# VGA_sound.net
KiCad netlist of a schematic drawn in EAGLE
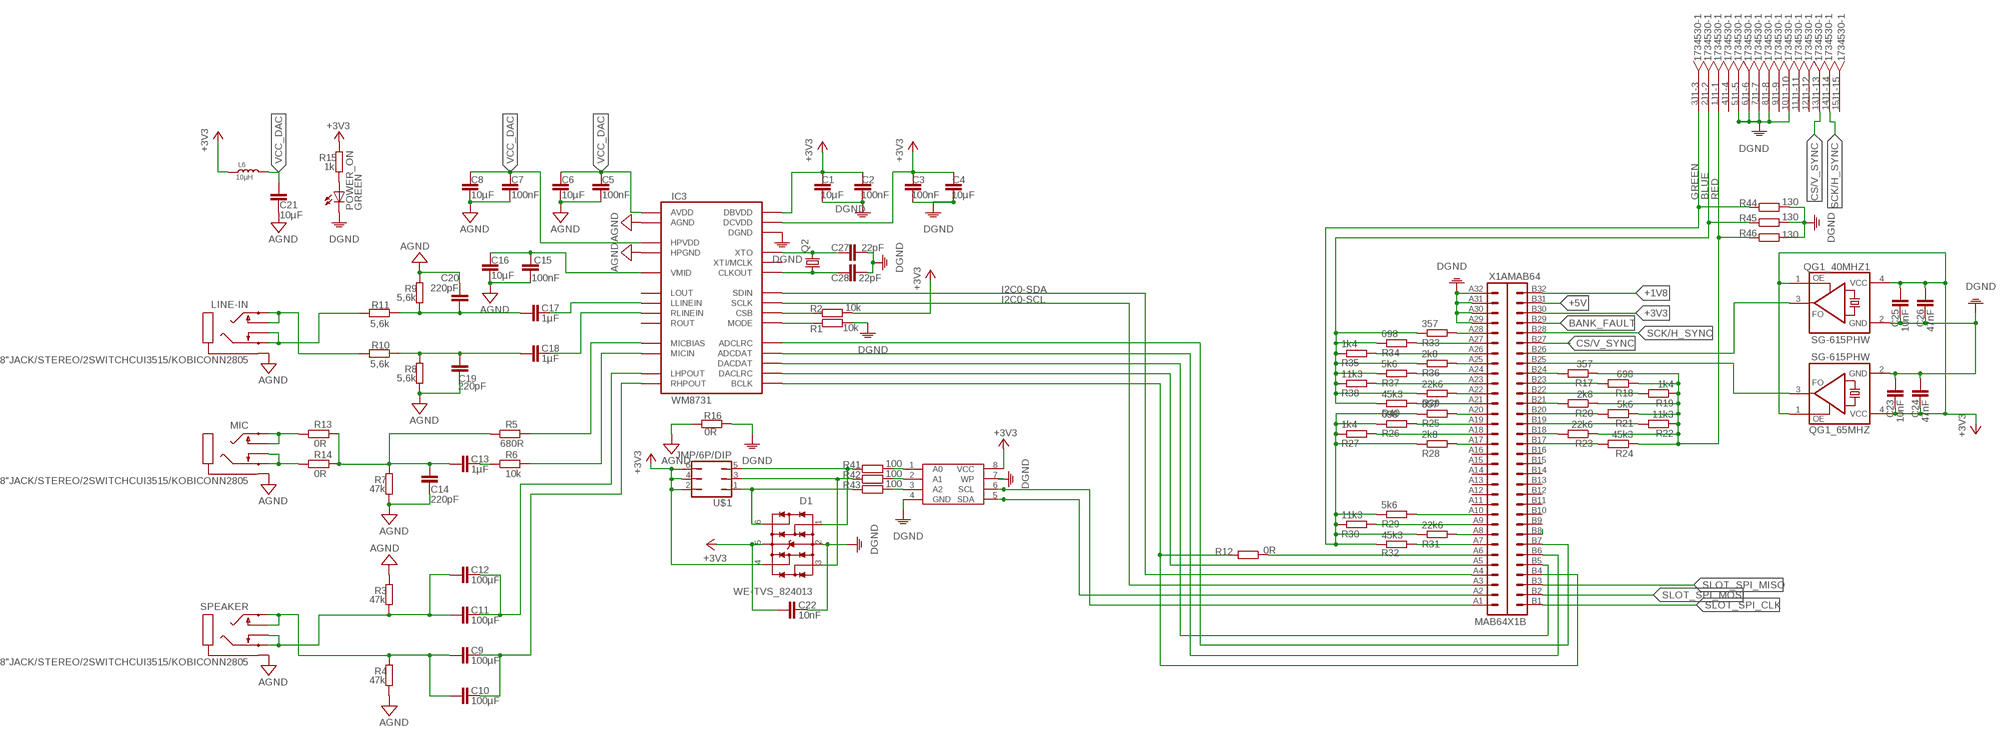
[diagram p0: schematic, sheet 1]

(export (version "E")
  (design (tool "Eeschema 10.0.6"))
  (components
    (comp (ref "C1")
      (value "10µF")
      (footprint "eagle-import:C0603")
      (libsource (lib "eagle-import") (part "C-EUC0603"))
    )
    (comp (ref "C2")
      (value "100nF")
      (footprint "eagle-import:C0603")
      (libsource (lib "eagle-import") (part "C-EUC0603"))
    )
    (comp (ref "C3")
      (value "100nF")
      (footprint "eagle-import:C0603K")
      (libsource (lib "eagle-import") (part "C-EUC0603K"))
    )
    (comp (ref "C4")
      (value "10µF")
      (footprint "eagle-import:C0603K")
      (libsource (lib "eagle-import") (part "C-EUC0603K"))
    )
    (comp (ref "C5")
      (value "100nF")
      (footprint "eagle-import:C0603K")
      (libsource (lib "eagle-import") (part "C-EUC0603K"))
    )
    (comp (ref "C6")
      (value "10µF")
      (footprint "eagle-import:C0603K")
      (libsource (lib "eagle-import") (part "C-EUC0603K"))
    )
    (comp (ref "C7")
      (value "100nF")
      (footprint "eagle-import:C0603K")
      (libsource (lib "eagle-import") (part "C-EUC0603K"))
    )
    (comp (ref "C8")
      (value "10µF")
      (footprint "eagle-import:C0603K")
      (libsource (lib "eagle-import") (part "C-EUC0603K"))
    )
    (comp (ref "C9")
      (value "100µF")
      (footprint "eagle-import:C1206")
      (libsource (lib "eagle-import") (part "C-EUC1206"))
    )
    (comp (ref "C10")
      (value "100µF")
      (footprint "eagle-import:C1206")
      (libsource (lib "eagle-import") (part "C-EUC1206"))
    )
    (comp (ref "C11")
      (value "100µF")
      (footprint "eagle-import:C1206")
      (libsource (lib "eagle-import") (part "C-EUC1206"))
    )
    (comp (ref "C12")
      (value "100µF")
      (footprint "eagle-import:C1206")
      (libsource (lib "eagle-import") (part "C-EUC1206"))
    )
    (comp (ref "C13")
      (value "1µF")
      (footprint "eagle-import:C0603")
      (libsource (lib "eagle-import") (part "C-EUC0603"))
    )
    (comp (ref "C14")
      (value "220pF")
      (footprint "eagle-import:C0603")
      (libsource (lib "eagle-import") (part "C-EUC0603"))
    )
    (comp (ref "C15")
      (value "100nF")
      (footprint "eagle-import:C0603")
      (libsource (lib "eagle-import") (part "C-EUC0603"))
    )
    (comp (ref "C16")
      (value "10µF")
      (footprint "eagle-import:C0603")
      (libsource (lib "eagle-import") (part "C-EUC0603"))
    )
    (comp (ref "C17")
      (value "1µF")
      (footprint "eagle-import:C0603")
      (libsource (lib "eagle-import") (part "C-EUC0603"))
    )
    (comp (ref "C18")
      (value "1µF")
      (footprint "eagle-import:C0603")
      (libsource (lib "eagle-import") (part "C-EUC0603"))
    )
    (comp (ref "C19")
      (value "220pF")
      (footprint "eagle-import:C0603")
      (libsource (lib "eagle-import") (part "C-EUC0603"))
    )
    (comp (ref "C20")
      (value "220pF")
      (footprint "eagle-import:C0603")
      (libsource (lib "eagle-import") (part "C-EUC0603"))
    )
    (comp (ref "C21")
      (value "10µF")
      (footprint "eagle-import:C0603")
      (libsource (lib "eagle-import") (part "C-EUC0603"))
    )
    (comp (ref "C22")
      (value "10nF")
      (footprint "eagle-import:C0603")
      (libsource (lib "eagle-import") (part "C-EUC0603"))
    )
    (comp (ref "C23")
      (value "10nF")
      (footprint "eagle-import:C0603")
      (libsource (lib "eagle-import") (part "C-EUC0603"))
    )
    (comp (ref "C24")
      (value "47nF")
      (footprint "eagle-import:C0603")
      (libsource (lib "eagle-import") (part "C-EUC0603"))
    )
    (comp (ref "C25")
      (value "10nF")
      (footprint "eagle-import:C0603")
      (libsource (lib "eagle-import") (part "C-EUC0603"))
    )
    (comp (ref "C26")
      (value "47nF")
      (footprint "eagle-import:C0603")
      (libsource (lib "eagle-import") (part "C-EUC0603"))
    )
    (comp (ref "C27")
      (value "22pF")
      (footprint "eagle-import:C0603")
      (libsource (lib "eagle-import") (part "C-EUC0603"))
    )
    (comp (ref "C28")
      (value "22pF")
      (footprint "eagle-import:C0603K")
      (libsource (lib "eagle-import") (part "C-EUC0603K"))
    )
    (comp (ref "D1")
      (value "WE-TVS_824013")
      (footprint "eagle-import:WE-TVS_SOT23-6L")
      (libsource (lib "eagle-import") (part "WE-TVS_824013"))
    )
    (comp (ref "IC1")
      (value "EEPROM")
      (footprint "eagle-import:SOIC-8")
      (libsource (lib "eagle-import") (part "EEPROM"))
    )
    (comp (ref "IC3")
      (value "WM8731")
      (footprint "eagle-import:28-SSOP")
      (libsource (lib "eagle-import") (part "WM8731"))
    )
    (comp (ref "J1")
      (value "1734530-1")
      (footprint "eagle-import:HD15_FEMALE_RIGHT-ANGLE")
      (fields (field (name "MANUFACTURER") "TE Connectivity") (field (name "PART_NUMBER") "1-1734530-1"))
      (libsource (lib "eagle-import") (part "1734530-1"))
    )
    (comp (ref "L6")
      (value "10µH")
      (footprint "eagle-import:L0805")
      (fields (field (name "MPN") "LQM2MPN2R2MG0"))
      (libsource (lib "eagle-import") (part "SMD-INDUCTOR-2.2UH-20%-1.2A(0805)"))
    )
    (comp (ref "LINE-IN")
      (value "1/8\"JACK/STEREO/2SWITCHCUI3515/KOBICONN2805")
      (footprint "eagle-import:1_8_JACK_STEREO_SMT")
      (libsource (lib "eagle-import") (part "1/8{dblquote}JACK/STEREO/2SWITCHCUI3515/KOBICONN2805"))
    )
    (comp (ref "MIC")
      (value "1/8\"JACK/STEREO/2SWITCHCUI3515/KOBICONN2805")
      (footprint "eagle-import:1_8_JACK_STEREO_SMT")
      (libsource (lib "eagle-import") (part "1/8{dblquote}JACK/STEREO/2SWITCHCUI3515/KOBICONN2805"))
    )
    (comp (ref "POWER_ON")
      (value "GREEN")
      (footprint "eagle-import:CHIP-LED0603")
      (libsource (lib "eagle-import") (part "LEDCHIP-LED0603"))
    )
    (comp (ref "Q2")
      (value "CRYTALSM49")
      (footprint "eagle-import:SM49")
      (libsource (lib "eagle-import") (part "CRYTALSM49"))
    )
    (comp (ref "QG1_40MHZ1")
      (value "SG-615PHW")
      (footprint "eagle-import:SG-615")
      (libsource (lib "eagle-import") (part "SG-615PHW"))
    )
    (comp (ref "QG1_65MHZ")
      (value "SG-615PHW")
      (footprint "eagle-import:SG-615")
      (libsource (lib "eagle-import") (part "SG-615PHW"))
    )
    (comp (ref "R1")
      (value "10k")
      (footprint "eagle-import:R0603")
      (libsource (lib "eagle-import") (part "R-EU_R0603"))
    )
    (comp (ref "R2")
      (value "10k")
      (footprint "eagle-import:R0603")
      (libsource (lib "eagle-import") (part "R-EU_R0603"))
    )
    (comp (ref "R3")
      (value "47k")
      (footprint "eagle-import:R0603")
      (libsource (lib "eagle-import") (part "R-EU_R0603"))
    )
    (comp (ref "R4")
      (value "47k")
      (footprint "eagle-import:R0603")
      (libsource (lib "eagle-import") (part "R-EU_R0603"))
    )
    (comp (ref "R5")
      (value "680R")
      (footprint "eagle-import:R0603")
      (libsource (lib "eagle-import") (part "R-EU_R0603"))
    )
    (comp (ref "R6")
      (value "10k")
      (footprint "eagle-import:R0603")
      (libsource (lib "eagle-import") (part "R-EU_R0603"))
    )
    (comp (ref "R7")
      (value "47k")
      (footprint "eagle-import:R0603")
      (libsource (lib "eagle-import") (part "R-EU_R0603"))
    )
    (comp (ref "R8")
      (value "5,6k")
      (footprint "eagle-import:R0603")
      (libsource (lib "eagle-import") (part "R-EU_R0603"))
    )
    (comp (ref "R9")
      (value "5,6k")
      (footprint "eagle-import:R0603")
      (libsource (lib "eagle-import") (part "R-EU_R0603"))
    )
    (comp (ref "R10")
      (value "5,6k")
      (footprint "eagle-import:R0603")
      (libsource (lib "eagle-import") (part "R-EU_R0603"))
    )
    (comp (ref "R11")
      (value "5,6k")
      (footprint "eagle-import:R0603")
      (libsource (lib "eagle-import") (part "R-EU_R0603"))
    )
    (comp (ref "R12")
      (value "0R")
      (footprint "eagle-import:R0603")
      (libsource (lib "eagle-import") (part "resistor_R-EU_R0603"))
    )
    (comp (ref "R13")
      (value "0R")
      (footprint "eagle-import:R0603")
      (libsource (lib "eagle-import") (part "resistor_R-EU_R0603"))
    )
    (comp (ref "R14")
      (value "0R")
      (footprint "eagle-import:R0603")
      (libsource (lib "eagle-import") (part "resistor_R-EU_R0603"))
    )
    (comp (ref "R15")
      (value "1k")
      (footprint "eagle-import:R0603")
      (libsource (lib "eagle-import") (part "resistor_R-EU_R0603"))
    )
    (comp (ref "R16")
      (value "0R")
      (footprint "eagle-import:R0603")
      (libsource (lib "eagle-import") (part "resistor_R-EU_R0603"))
    )
    (comp (ref "R17")
      (value "357")
      (footprint "eagle-import:R0603")
      (libsource (lib "eagle-import") (part "resistor_R-EU_R0603"))
    )
    (comp (ref "R18")
      (value "698")
      (footprint "eagle-import:R0603")
      (libsource (lib "eagle-import") (part "resistor_R-EU_R0603"))
    )
    (comp (ref "R19")
      (value "1k4")
      (footprint "eagle-import:R0603")
      (libsource (lib "eagle-import") (part "resistor_R-EU_R0603"))
    )
    (comp (ref "R20")
      (value "2k8")
      (footprint "eagle-import:R0603")
      (libsource (lib "eagle-import") (part "resistor_R-EU_R0603"))
    )
    (comp (ref "R21")
      (value "5k6")
      (footprint "eagle-import:R0603")
      (libsource (lib "eagle-import") (part "resistor_R-EU_R0603"))
    )
    (comp (ref "R22")
      (value "11k3")
      (footprint "eagle-import:R0603")
      (libsource (lib "eagle-import") (part "resistor_R-EU_R0603"))
    )
    (comp (ref "R23")
      (value "22k6")
      (footprint "eagle-import:R0603")
      (libsource (lib "eagle-import") (part "resistor_R-EU_R0603"))
    )
    (comp (ref "R24")
      (value "45k3")
      (footprint "eagle-import:R0603")
      (libsource (lib "eagle-import") (part "resistor_R-EU_R0603"))
    )
    (comp (ref "R25")
      (value "357")
      (footprint "eagle-import:R0603")
      (libsource (lib "eagle-import") (part "resistor_R-EU_R0603"))
    )
    (comp (ref "R26")
      (value "698")
      (footprint "eagle-import:R0603")
      (libsource (lib "eagle-import") (part "resistor_R-EU_R0603"))
    )
    (comp (ref "R27")
      (value "1k4")
      (footprint "eagle-import:R0603")
      (libsource (lib "eagle-import") (part "resistor_R-EU_R0603"))
    )
    (comp (ref "R28")
      (value "2k8")
      (footprint "eagle-import:R0603")
      (libsource (lib "eagle-import") (part "resistor_R-EU_R0603"))
    )
    (comp (ref "R29")
      (value "5k6")
      (footprint "eagle-import:R0603")
      (libsource (lib "eagle-import") (part "resistor_R-EU_R0603"))
    )
    (comp (ref "R30")
      (value "11k3")
      (footprint "eagle-import:R0603")
      (libsource (lib "eagle-import") (part "resistor_R-EU_R0603"))
    )
    (comp (ref "R31")
      (value "22k6")
      (footprint "eagle-import:R0603")
      (libsource (lib "eagle-import") (part "resistor_R-EU_R0603"))
    )
    (comp (ref "R32")
      (value "45k3")
      (footprint "eagle-import:R0603")
      (libsource (lib "eagle-import") (part "resistor_R-EU_R0603"))
    )
    (comp (ref "R33")
      (value "357")
      (footprint "eagle-import:R0603")
      (libsource (lib "eagle-import") (part "resistor_R-EU_R0603"))
    )
    (comp (ref "R34")
      (value "698")
      (footprint "eagle-import:R0603")
      (libsource (lib "eagle-import") (part "resistor_R-EU_R0603"))
    )
    (comp (ref "R35")
      (value "1k4")
      (footprint "eagle-import:R0603")
      (libsource (lib "eagle-import") (part "resistor_R-EU_R0603"))
    )
    (comp (ref "R36")
      (value "2k8")
      (footprint "eagle-import:R0603")
      (libsource (lib "eagle-import") (part "resistor_R-EU_R0603"))
    )
    (comp (ref "R37")
      (value "5k6")
      (footprint "eagle-import:R0603")
      (libsource (lib "eagle-import") (part "resistor_R-EU_R0603"))
    )
    (comp (ref "R38")
      (value "11k3")
      (footprint "eagle-import:R0603")
      (libsource (lib "eagle-import") (part "resistor_R-EU_R0603"))
    )
    (comp (ref "R39")
      (value "22k6")
      (footprint "eagle-import:R0603")
      (libsource (lib "eagle-import") (part "resistor_R-EU_R0603"))
    )
    (comp (ref "R40")
      (value "45k3")
      (footprint "eagle-import:R0603")
      (libsource (lib "eagle-import") (part "resistor_R-EU_R0603"))
    )
    (comp (ref "R41")
      (value "100")
      (footprint "eagle-import:R0603")
      (libsource (lib "eagle-import") (part "R-EU_R0603"))
    )
    (comp (ref "R42")
      (value "100")
      (footprint "eagle-import:R0603")
      (libsource (lib "eagle-import") (part "R-EU_R0603"))
    )
    (comp (ref "R43")
      (value "100")
      (footprint "eagle-import:R0603")
      (libsource (lib "eagle-import") (part "R-EU_R0603"))
    )
    (comp (ref "R44")
      (value "130")
      (footprint "eagle-import:R0603")
      (libsource (lib "eagle-import") (part "resistor_R-EU_R0603"))
    )
    (comp (ref "R45")
      (value "130")
      (footprint "eagle-import:R0603")
      (libsource (lib "eagle-import") (part "resistor_R-EU_R0603"))
    )
    (comp (ref "R46")
      (value "130")
      (footprint "eagle-import:R0603")
      (libsource (lib "eagle-import") (part "resistor_R-EU_R0603"))
    )
    (comp (ref "SPEAKER")
      (value "1/8\"JACK/STEREO/2SWITCHCUI3515/KOBICONN2805")
      (footprint "eagle-import:1_8_JACK_STEREO_SMT")
      (libsource (lib "eagle-import") (part "1/8{dblquote}JACK/STEREO/2SWITCHCUI3515/KOBICONN2805"))
    )
    (comp (ref "U$1")
      (value "JMP/6P/DIP")
      (footprint "eagle-import:JMP_6P_DIP")
      (libsource (lib "eagle-import") (part "JMP/6P/DIP"))
    )
    (comp (ref "X1")
      (value "MAB64")
      (footprint "eagle-import:MAB64")
      (libsource (lib "eagle-import") (part "MAB64"))
    )
  )
  (nets
    (net (code "1") (name "+1V8") (class "Default")
      (node (ref "X1") (pin "B32") (pinfunction "32_B32") (pintype "passive"))
    )
    (net (code "2") (name "+3V3") (class "Default")
      (node (ref "C1") (pin "2") (pinfunction "2_2") (pintype "passive"))
      (node (ref "C2") (pin "2") (pinfunction "2_2") (pintype "passive"))
      (node (ref "C22") (pin "2") (pinfunction "2_2") (pintype "passive"))
      (node (ref "C23") (pin "1") (pinfunction "1_1") (pintype "passive"))
      (node (ref "C24") (pin "1") (pinfunction "1_1") (pintype "passive"))
      (node (ref "C25") (pin "2") (pinfunction "2_2") (pintype "passive"))
      (node (ref "C26") (pin "2") (pinfunction "2_2") (pintype "passive"))
      (node (ref "C3") (pin "2") (pinfunction "2_2") (pintype "passive"))
      (node (ref "C4") (pin "2") (pinfunction "2_2") (pintype "passive"))
      (node (ref "D1") (pin "4") (pinfunction "3_4") (pintype "passive"))
      (node (ref "D1") (pin "5") (pinfunction "VDD_5") (pintype "power_in"))
      (node (ref "IC1") (pin "8") (pinfunction "VCC_8") (pintype "bidirectional"))
      (node (ref "IC3") (pin "P$1") (pinfunction "DBVDD_P$1") (pintype "power_in"))
      (node (ref "IC3") (pin "P$27") (pinfunction "DCVDD_P$27") (pintype "power_in"))
      (node (ref "L6") (pin "1") (pinfunction "1_1") (pintype "passive"))
      (node (ref "QG1_40MHZ1") (pin "1") (pinfunction "OE_1") (pintype "input"))
      (node (ref "QG1_40MHZ1") (pin "4") (pinfunction "VCC_4") (pintype "power_in"))
      (node (ref "QG1_65MHZ") (pin "1") (pinfunction "OE_1") (pintype "input"))
      (node (ref "QG1_65MHZ") (pin "4") (pinfunction "VCC_4") (pintype "power_in"))
      (node (ref "R15") (pin "2") (pinfunction "2_2") (pintype "passive"))
      (node (ref "R2") (pin "2") (pinfunction "2_2") (pintype "passive"))
      (node (ref "U$1") (pin "2") (pinfunction "2_2") (pintype "passive"))
      (node (ref "U$1") (pin "4") (pinfunction "4_4") (pintype "passive"))
      (node (ref "U$1") (pin "6") (pinfunction "6_6") (pintype "passive"))
      (node (ref "X1") (pin "B30") (pinfunction "30_B30") (pintype "passive"))
    )
    (net (code "3") (name "+5V") (class "Default")
      (node (ref "X1") (pin "B31") (pinfunction "31_B31") (pintype "passive"))
    )
    (net (code "4") (name "/I2C0-SCL") (class "Default")
      (node (ref "IC3") (pin "P$24") (pinfunction "SCLK_P$24") (pintype "input"))
      (node (ref "X1") (pin "A3") (pinfunction "3_A3") (pintype "passive"))
    )
    (net (code "5") (name "/I2C0-SDA") (class "Default")
      (node (ref "IC3") (pin "P$23") (pinfunction "SDIN_P$23") (pintype "bidirectional"))
      (node (ref "X1") (pin "A4") (pinfunction "4_A4") (pintype "passive"))
    )
    (net (code "6") (name "AGND") (class "Default")
      (node (ref "C14") (pin "1") (pinfunction "1_1") (pintype "passive"))
      (node (ref "C15") (pin "1") (pinfunction "1_1") (pintype "passive"))
      (node (ref "C16") (pin "1") (pinfunction "1_1") (pintype "passive"))
      (node (ref "C19") (pin "2") (pinfunction "2_2") (pintype "passive"))
      (node (ref "C20") (pin "1") (pinfunction "1_1") (pintype "passive"))
      (node (ref "C21") (pin "1") (pinfunction "1_1") (pintype "passive"))
      (node (ref "C5") (pin "1") (pinfunction "1_1") (pintype "passive"))
      (node (ref "C6") (pin "1") (pinfunction "1_1") (pintype "passive"))
      (node (ref "C7") (pin "1") (pinfunction "1_1") (pintype "passive"))
      (node (ref "C8") (pin "1") (pinfunction "1_1") (pintype "passive"))
      (node (ref "IC3") (pin "P$11") (pinfunction "HPGND_P$11") (pintype "power_in"))
      (node (ref "IC3") (pin "P$15") (pinfunction "AGND_P$15") (pintype "power_in"))
      (node (ref "LINE-IN") (pin "P$1") (pinfunction "1_P$1") (pintype "passive"))
      (node (ref "MIC") (pin "P$1") (pinfunction "1_P$1") (pintype "passive"))
      (node (ref "R16") (pin "2") (pinfunction "2_2") (pintype "passive"))
      (node (ref "R3") (pin "2") (pinfunction "2_2") (pintype "passive"))
      (node (ref "R4") (pin "1") (pinfunction "1_1") (pintype "passive"))
      (node (ref "R7") (pin "1") (pinfunction "1_1") (pintype "passive"))
      (node (ref "R8") (pin "1") (pinfunction "1_1") (pintype "passive"))
      (node (ref "R9") (pin "2") (pinfunction "2_2") (pintype "passive"))
      (node (ref "SPEAKER") (pin "P$1") (pinfunction "1_P$1") (pintype "passive"))
    )
    (net (code "7") (name "BANK_FAULT") (class "Default")
      (node (ref "X1") (pin "B29") (pinfunction "29_B29") (pintype "passive"))
    )
    (net (code "8") (name "CS{slash}V_SYNC") (class "Default")
      (node (ref "J1") (pin "13") (pinfunction "P$1_13") (pintype "bidirectional"))
      (node (ref "X1") (pin "B27") (pinfunction "27_B27") (pintype "passive"))
    )
    (net (code "9") (name "DGND") (class "Default")
      (node (ref "C1") (pin "1") (pinfunction "1_1") (pintype "passive"))
      (node (ref "C2") (pin "1") (pinfunction "1_1") (pintype "passive"))
      (node (ref "C22") (pin "1") (pinfunction "1_1") (pintype "passive"))
      (node (ref "C23") (pin "2") (pinfunction "2_2") (pintype "passive"))
      (node (ref "C24") (pin "2") (pinfunction "2_2") (pintype "passive"))
      (node (ref "C25") (pin "1") (pinfunction "1_1") (pintype "passive"))
      (node (ref "C26") (pin "1") (pinfunction "1_1") (pintype "passive"))
      (node (ref "C27") (pin "1") (pinfunction "1_1") (pintype "passive"))
      (node (ref "C28") (pin "1") (pinfunction "1_1") (pintype "passive"))
      (node (ref "C3") (pin "1") (pinfunction "1_1") (pintype "passive"))
      (node (ref "C4") (pin "1") (pinfunction "1_1") (pintype "passive"))
      (node (ref "D1") (pin "2") (pinfunction "GND_2") (pintype "power_in"))
      (node (ref "IC1") (pin "4") (pinfunction "GND_4") (pintype "bidirectional"))
      (node (ref "IC1") (pin "7") (pinfunction "WP_7") (pintype "bidirectional"))
      (node (ref "IC3") (pin "P$28") (pinfunction "DGND_P$28") (pintype "power_in"))
      (node (ref "J1") (pin "10") (pinfunction "P$1_10") (pintype "bidirectional"))
      (node (ref "J1") (pin "5") (pinfunction "P$1_5") (pintype "bidirectional"))
      (node (ref "J1") (pin "6") (pinfunction "P$1_6") (pintype "bidirectional"))
      (node (ref "J1") (pin "7") (pinfunction "P$1_7") (pintype "bidirectional"))
      (node (ref "J1") (pin "8") (pinfunction "P$1_8") (pintype "bidirectional"))
      (node (ref "POWER_ON") (pin "C") (pinfunction "C_C") (pintype "passive"))
      (node (ref "QG1_40MHZ1") (pin "2") (pinfunction "GND_2") (pintype "power_in"))
      (node (ref "QG1_65MHZ") (pin "2") (pinfunction "GND_2") (pintype "power_in"))
      (node (ref "R1") (pin "2") (pinfunction "2_2") (pintype "passive"))
      (node (ref "R16") (pin "1") (pinfunction "1_1") (pintype "passive"))
      (node (ref "R44") (pin "2") (pinfunction "2_2") (pintype "passive"))
      (node (ref "R45") (pin "2") (pinfunction "2_2") (pintype "passive"))
      (node (ref "R46") (pin "2") (pinfunction "2_2") (pintype "passive"))
      (node (ref "X1") (pin "A29") (pinfunction "29_A29") (pintype "passive"))
      (node (ref "X1") (pin "A30") (pinfunction "30_A30") (pintype "passive"))
      (node (ref "X1") (pin "A31") (pinfunction "31_A31") (pintype "passive"))
      (node (ref "X1") (pin "A32") (pinfunction "32_A32") (pintype "passive"))
    )
    (net (code "10") (name "Net-(C13-Pad1)") (class "Default")
      (node (ref "C13") (pin "1") (pinfunction "1_1") (pintype "passive"))
      (node (ref "R6") (pin "1") (pinfunction "1_1") (pintype "passive"))
    )
    (net (code "11") (name "Net-(C13-Pad2)") (class "Default")
      (node (ref "C13") (pin "2") (pinfunction "2_2") (pintype "passive"))
      (node (ref "C14") (pin "2") (pinfunction "2_2") (pintype "passive"))
      (node (ref "R13") (pin "2") (pinfunction "2_2") (pintype "passive"))
      (node (ref "R14") (pin "2") (pinfunction "2_2") (pintype "passive"))
      (node (ref "R5") (pin "1") (pinfunction "1_1") (pintype "passive"))
      (node (ref "R7") (pin "2") (pinfunction "2_2") (pintype "passive"))
    )
    (net (code "12") (name "Net-(C17-Pad2)") (class "Default")
      (node (ref "C17") (pin "2") (pinfunction "2_2") (pintype "passive"))
      (node (ref "C20") (pin "2") (pinfunction "2_2") (pintype "passive"))
      (node (ref "R11") (pin "1") (pinfunction "1_1") (pintype "passive"))
      (node (ref "R9") (pin "1") (pinfunction "1_1") (pintype "passive"))
    )
    (net (code "13") (name "Net-(C18-Pad2)") (class "Default")
      (node (ref "C18") (pin "2") (pinfunction "2_2") (pintype "passive"))
      (node (ref "C19") (pin "1") (pinfunction "1_1") (pintype "passive"))
      (node (ref "R10") (pin "1") (pinfunction "1_1") (pintype "passive"))
      (node (ref "R8") (pin "2") (pinfunction "2_2") (pintype "passive"))
    )
    (net (code "14") (name "Net-(D1-2)") (class "Default")
      (node (ref "D1") (pin "3") (pinfunction "2_3") (pintype "passive"))
      (node (ref "R42") (pin "1") (pinfunction "1_1") (pintype "passive"))
      (node (ref "U$1") (pin "3") (pinfunction "3_3") (pintype "passive"))
    )
    (net (code "15") (name "Net-(D1-4)") (class "Default")
      (node (ref "D1") (pin "6") (pinfunction "4_6") (pintype "passive"))
      (node (ref "R43") (pin "1") (pinfunction "1_1") (pintype "passive"))
      (node (ref "U$1") (pin "1") (pinfunction "1_1") (pintype "passive"))
    )
    (net (code "16") (name "Net-(D1-Pad1)") (class "Default")
      (node (ref "D1") (pin "1") (pinfunction "1_1") (pintype "passive"))
      (node (ref "R41") (pin "1") (pinfunction "1_1") (pintype "passive"))
      (node (ref "U$1") (pin "5") (pinfunction "5_5") (pintype "passive"))
    )
    (net (code "17") (name "Net-(IC1-A0)") (class "Default")
      (node (ref "IC1") (pin "1") (pinfunction "A0_1") (pintype "bidirectional"))
      (node (ref "R41") (pin "2") (pinfunction "2_2") (pintype "passive"))
    )
    (net (code "18") (name "Net-(IC1-A1)") (class "Default")
      (node (ref "IC1") (pin "2") (pinfunction "A1_2") (pintype "bidirectional"))
      (node (ref "R42") (pin "2") (pinfunction "2_2") (pintype "passive"))
    )
    (net (code "19") (name "Net-(IC1-A2)") (class "Default")
      (node (ref "IC1") (pin "3") (pinfunction "A2_3") (pintype "bidirectional"))
      (node (ref "R43") (pin "2") (pinfunction "2_2") (pintype "passive"))
    )
    (net (code "20") (name "Net-(IC1-SCL)") (class "Default")
      (node (ref "IC1") (pin "6") (pinfunction "SCL_6") (pintype "bidirectional"))
      (node (ref "X1") (pin "A1") (pinfunction "1_A1") (pintype "passive"))
    )
    (net (code "21") (name "Net-(IC1-SDA)") (class "Default")
      (node (ref "IC1") (pin "5") (pinfunction "SDA_5") (pintype "bidirectional"))
      (node (ref "X1") (pin "A2") (pinfunction "2_A2") (pintype "passive"))
    )
    (net (code "22") (name "Net-(IC3-ADCDAT)") (class "Default")
      (node (ref "IC3") (pin "P$6") (pinfunction "ADCDAT_P$6") (pintype "output"))
      (node (ref "X1") (pin "B6") (pinfunction "6_B6") (pintype "passive"))
    )
    (net (code "23") (name "Net-(IC3-ADCLRC)") (class "Default")
      (node (ref "IC3") (pin "P$7") (pinfunction "ADCLRC_P$7") (pintype "bidirectional"))
      (node (ref "X1") (pin "B7") (pinfunction "7_B7") (pintype "passive"))
    )
    (net (code "24") (name "Net-(IC3-BCLK)") (class "Default")
      (node (ref "IC3") (pin "P$3") (pinfunction "BCLK_P$3") (pintype "bidirectional"))
      (node (ref "R12") (pin "2") (pinfunction "2_2") (pintype "passive"))
      (node (ref "X1") (pin "B4") (pinfunction "4_B4") (pintype "passive"))
    )
    (net (code "25") (name "Net-(IC3-CLKOUT)") (class "Default")
      (node (ref "C28") (pin "2") (pinfunction "2_2") (pintype "passive"))
      (node (ref "IC3") (pin "P$2") (pinfunction "CLKOUT_P$2") (pintype "output"))
      (node (ref "Q2") (pin "1") (pinfunction "1_1") (pintype "passive"))
    )
    (net (code "26") (name "Net-(IC3-CSB)") (class "Default")
      (node (ref "IC3") (pin "P$22") (pinfunction "CSB_P$22") (pintype "input"))
      (node (ref "R2") (pin "1") (pinfunction "1_1") (pintype "passive"))
    )
    (net (code "27") (name "Net-(IC3-DACDAT)") (class "Default")
      (node (ref "IC3") (pin "P$4") (pinfunction "DACDAT_P$4") (pintype "input"))
      (node (ref "X1") (pin "B5") (pinfunction "5_B5") (pintype "passive"))
    )
    (net (code "28") (name "Net-(IC3-DACLRC)") (class "Default")
      (node (ref "IC3") (pin "P$5") (pinfunction "DACLRC_P$5") (pintype "bidirectional"))
      (node (ref "X1") (pin "A5") (pinfunction "5_A5") (pintype "passive"))
    )
    (net (code "29") (name "Net-(IC3-LHPOUT)") (class "Default")
      (node (ref "C11") (pin "1") (pinfunction "1_1") (pintype "passive"))
      (node (ref "C12") (pin "1") (pinfunction "1_1") (pintype "passive"))
      (node (ref "IC3") (pin "P$9") (pinfunction "LHPOUT_P$9") (pintype "output"))
    )
    (net (code "30") (name "Net-(IC3-LLINEIN)") (class "Default")
      (node (ref "C17") (pin "1") (pinfunction "1_1") (pintype "passive"))
      (node (ref "IC3") (pin "P$20") (pinfunction "LLINEIN_P$20") (pintype "input"))
    )
    (net (code "31") (name "Net-(IC3-MICBIAS)") (class "Default")
      (node (ref "IC3") (pin "P$17") (pinfunction "MICBIAS_P$17") (pintype "output"))
      (node (ref "R5") (pin "2") (pinfunction "2_2") (pintype "passive"))
    )
    (net (code "32") (name "Net-(IC3-MICIN)") (class "Default")
      (node (ref "IC3") (pin "P$18") (pinfunction "MICIN_P$18") (pintype "input"))
      (node (ref "R6") (pin "2") (pinfunction "2_2") (pintype "passive"))
    )
    (net (code "33") (name "Net-(IC3-MODE)") (class "Default")
      (node (ref "IC3") (pin "P$21") (pinfunction "MODE_P$21") (pintype "input"))
      (node (ref "R1") (pin "1") (pinfunction "1_1") (pintype "passive"))
    )
    (net (code "34") (name "Net-(IC3-RHPOUT)") (class "Default")
      (node (ref "C10") (pin "1") (pinfunction "1_1") (pintype "passive"))
      (node (ref "C9") (pin "1") (pinfunction "1_1") (pintype "passive"))
      (node (ref "IC3") (pin "P$10") (pinfunction "RHPOUT_P$10") (pintype "output"))
    )
    (net (code "35") (name "Net-(IC3-RLINEIN)") (class "Default")
      (node (ref "C18") (pin "1") (pinfunction "1_1") (pintype "passive"))
      (node (ref "IC3") (pin "P$19") (pinfunction "RLINEIN_P$19") (pintype "input"))
    )
    (net (code "36") (name "Net-(IC3-VMID)") (class "Default")
      (node (ref "C15") (pin "2") (pinfunction "2_2") (pintype "passive"))
      (node (ref "C16") (pin "2") (pinfunction "2_2") (pintype "passive"))
      (node (ref "IC3") (pin "P$16") (pinfunction "VMID_P$16") (pintype "output"))
    )
    (net (code "37") (name "Net-(IC3-XTO)") (class "Default")
      (node (ref "C27") (pin "2") (pinfunction "2_2") (pintype "passive"))
      (node (ref "IC3") (pin "P$26") (pinfunction "XTO_P$26") (pintype "output"))
      (node (ref "Q2") (pin "2") (pinfunction "2_2") (pintype "passive"))
    )
    (net (code "38") (name "Net-(J1A-P$1)") (class "Default")
      (node (ref "J1") (pin "1") (pinfunction "P$1_1") (pintype "bidirectional"))
      (node (ref "R17") (pin "1") (pinfunction "1_1") (pintype "passive"))
      (node (ref "R18") (pin "1") (pinfunction "1_1") (pintype "passive"))
      (node (ref "R19") (pin "1") (pinfunction "1_1") (pintype "passive"))
      (node (ref "R20") (pin "1") (pinfunction "1_1") (pintype "passive"))
      (node (ref "R21") (pin "1") (pinfunction "1_1") (pintype "passive"))
      (node (ref "R22") (pin "1") (pinfunction "1_1") (pintype "passive"))
      (node (ref "R23") (pin "1") (pinfunction "1_1") (pintype "passive"))
      (node (ref "R24") (pin "1") (pinfunction "1_1") (pintype "passive"))
      (node (ref "R46") (pin "1") (pinfunction "1_1") (pintype "passive"))
    )
    (net (code "39") (name "Net-(J1H-P$1)") (class "Default")
      (node (ref "J1") (pin "2") (pinfunction "P$1_2") (pintype "bidirectional"))
      (node (ref "R33") (pin "1") (pinfunction "1_1") (pintype "passive"))
      (node (ref "R34") (pin "1") (pinfunction "1_1") (pintype "passive"))
      (node (ref "R35") (pin "1") (pinfunction "1_1") (pintype "passive"))
      (node (ref "R36") (pin "1") (pinfunction "1_1") (pintype "passive"))
      (node (ref "R37") (pin "1") (pinfunction "1_1") (pintype "passive"))
      (node (ref "R38") (pin "1") (pinfunction "1_1") (pintype "passive"))
      (node (ref "R39") (pin "1") (pinfunction "1_1") (pintype "passive"))
      (node (ref "R40") (pin "1") (pinfunction "1_1") (pintype "passive"))
      (node (ref "R45") (pin "1") (pinfunction "1_1") (pintype "passive"))
    )
    (net (code "40") (name "Net-(J1I-P$1)") (class "Default")
      (node (ref "J1") (pin "3") (pinfunction "P$1_3") (pintype "bidirectional"))
      (node (ref "R25") (pin "1") (pinfunction "1_1") (pintype "passive"))
      (node (ref "R26") (pin "1") (pinfunction "1_1") (pintype "passive"))
      (node (ref "R27") (pin "1") (pinfunction "1_1") (pintype "passive"))
      (node (ref "R28") (pin "1") (pinfunction "1_1") (pintype "passive"))
      (node (ref "R29") (pin "1") (pinfunction "1_1") (pintype "passive"))
      (node (ref "R30") (pin "1") (pinfunction "1_1") (pintype "passive"))
      (node (ref "R31") (pin "1") (pinfunction "1_1") (pintype "passive"))
      (node (ref "R32") (pin "1") (pinfunction "1_1") (pintype "passive"))
      (node (ref "R44") (pin "1") (pinfunction "1_1") (pintype "passive"))
    )
    (net (code "41") (name "Net-(LINE-IN-2)") (class "Default")
      (node (ref "LINE-IN") (pin "P$2") (pinfunction "3_P$2") (pintype "passive"))
      (node (ref "LINE-IN") (pin "P$3") (pinfunction "2_P$3") (pintype "passive"))
      (node (ref "R11") (pin "2") (pinfunction "2_2") (pintype "passive"))
    )
    (net (code "42") (name "Net-(LINE-IN-4)") (class "Default")
      (node (ref "LINE-IN") (pin "P$4") (pinfunction "4_P$4") (pintype "passive"))
      (node (ref "LINE-IN") (pin "P$5") (pinfunction "5_P$5") (pintype "passive"))
      (node (ref "R10") (pin "2") (pinfunction "2_2") (pintype "passive"))
    )
    (net (code "43") (name "Net-(MIC-2)") (class "Default")
      (node (ref "MIC") (pin "P$2") (pinfunction "3_P$2") (pintype "passive"))
      (node (ref "MIC") (pin "P$3") (pinfunction "2_P$3") (pintype "passive"))
      (node (ref "R14") (pin "1") (pinfunction "1_1") (pintype "passive"))
    )
    (net (code "44") (name "Net-(MIC-4)") (class "Default")
      (node (ref "MIC") (pin "P$4") (pinfunction "4_P$4") (pintype "passive"))
      (node (ref "MIC") (pin "P$5") (pinfunction "5_P$5") (pintype "passive"))
      (node (ref "R13") (pin "1") (pinfunction "1_1") (pintype "passive"))
    )
    (net (code "45") (name "Net-(POWER_ON-PadA)") (class "Default")
      (node (ref "POWER_ON") (pin "A") (pinfunction "A_A") (pintype "passive"))
      (node (ref "R15") (pin "1") (pinfunction "1_1") (pintype "passive"))
    )
    (net (code "46") (name "Net-(QG1_40MHZ1-FO)") (class "Default")
      (node (ref "QG1_40MHZ1") (pin "3") (pinfunction "FO_3") (pintype "output"))
      (node (ref "X1") (pin "B26") (pinfunction "26_B26") (pintype "passive"))
    )
    (net (code "47") (name "Net-(QG1_65MHZ-FO)") (class "Default")
      (node (ref "QG1_65MHZ") (pin "3") (pinfunction "FO_3") (pintype "output"))
      (node (ref "X1") (pin "B25") (pinfunction "25_B25") (pintype "passive"))
    )
    (net (code "48") (name "Net-(SPEAKER-2)") (class "Default")
      (node (ref "C11") (pin "2") (pinfunction "2_2") (pintype "passive"))
      (node (ref "C12") (pin "2") (pinfunction "2_2") (pintype "passive"))
      (node (ref "R3") (pin "1") (pinfunction "1_1") (pintype "passive"))
      (node (ref "SPEAKER") (pin "P$2") (pinfunction "3_P$2") (pintype "passive"))
      (node (ref "SPEAKER") (pin "P$3") (pinfunction "2_P$3") (pintype "passive"))
    )
    (net (code "49") (name "Net-(SPEAKER-4)") (class "Default")
      (node (ref "C10") (pin "2") (pinfunction "2_2") (pintype "passive"))
      (node (ref "C9") (pin "2") (pinfunction "2_2") (pintype "passive"))
      (node (ref "R4") (pin "2") (pinfunction "2_2") (pintype "passive"))
      (node (ref "SPEAKER") (pin "P$4") (pinfunction "4_P$4") (pintype "passive"))
      (node (ref "SPEAKER") (pin "P$5") (pinfunction "5_P$5") (pintype "passive"))
    )
    (net (code "50") (name "Net-(X1A-6)") (class "Default")
      (node (ref "R12") (pin "1") (pinfunction "1_1") (pintype "passive"))
      (node (ref "X1") (pin "A6") (pinfunction "6_A6") (pintype "passive"))
    )
    (net (code "51") (name "Net-(X1A-7)") (class "Default")
      (node (ref "R32") (pin "2") (pinfunction "2_2") (pintype "passive"))
      (node (ref "X1") (pin "A7") (pinfunction "7_A7") (pintype "passive"))
    )
    (net (code "52") (name "Net-(X1A-8)") (class "Default")
      (node (ref "R31") (pin "2") (pinfunction "2_2") (pintype "passive"))
      (node (ref "X1") (pin "A8") (pinfunction "8_A8") (pintype "passive"))
    )
    (net (code "53") (name "Net-(X1A-9)") (class "Default")
      (node (ref "R30") (pin "2") (pinfunction "2_2") (pintype "passive"))
      (node (ref "X1") (pin "A9") (pinfunction "9_A9") (pintype "passive"))
    )
    (net (code "54") (name "Net-(X1A-10)") (class "Default")
      (node (ref "R29") (pin "2") (pinfunction "2_2") (pintype "passive"))
      (node (ref "X1") (pin "A10") (pinfunction "10_A10") (pintype "passive"))
    )
    (net (code "55") (name "Net-(X1A-17)") (class "Default")
      (node (ref "R28") (pin "2") (pinfunction "2_2") (pintype "passive"))
      (node (ref "X1") (pin "A17") (pinfunction "17_A17") (pintype "passive"))
    )
    (net (code "56") (name "Net-(X1A-18)") (class "Default")
      (node (ref "R27") (pin "2") (pinfunction "2_2") (pintype "passive"))
      (node (ref "X1") (pin "A18") (pinfunction "18_A18") (pintype "passive"))
    )
    (net (code "57") (name "Net-(X1A-19)") (class "Default")
      (node (ref "R26") (pin "2") (pinfunction "2_2") (pintype "passive"))
      (node (ref "X1") (pin "A19") (pinfunction "19_A19") (pintype "passive"))
    )
    (net (code "58") (name "Net-(X1A-20)") (class "Default")
      (node (ref "R25") (pin "2") (pinfunction "2_2") (pintype "passive"))
      (node (ref "X1") (pin "A20") (pinfunction "20_A20") (pintype "passive"))
    )
    (net (code "59") (name "Net-(X1A-21)") (class "Default")
      (node (ref "R40") (pin "2") (pinfunction "2_2") (pintype "passive"))
      (node (ref "X1") (pin "A21") (pinfunction "21_A21") (pintype "passive"))
    )
    (net (code "60") (name "Net-(X1A-22)") (class "Default")
      (node (ref "R39") (pin "2") (pinfunction "2_2") (pintype "passive"))
      (node (ref "X1") (pin "A22") (pinfunction "22_A22") (pintype "passive"))
    )
    (net (code "61") (name "Net-(X1A-23)") (class "Default")
      (node (ref "R38") (pin "2") (pinfunction "2_2") (pintype "passive"))
      (node (ref "X1") (pin "A23") (pinfunction "23_A23") (pintype "passive"))
    )
    (net (code "62") (name "Net-(X1A-24)") (class "Default")
      (node (ref "R37") (pin "2") (pinfunction "2_2") (pintype "passive"))
      (node (ref "X1") (pin "A24") (pinfunction "24_A24") (pintype "passive"))
    )
    (net (code "63") (name "Net-(X1A-25)") (class "Default")
      (node (ref "R36") (pin "2") (pinfunction "2_2") (pintype "passive"))
      (node (ref "X1") (pin "A25") (pinfunction "25_A25") (pintype "passive"))
    )
    (net (code "64") (name "Net-(X1A-26)") (class "Default")
      (node (ref "R35") (pin "2") (pinfunction "2_2") (pintype "passive"))
      (node (ref "X1") (pin "A26") (pinfunction "26_A26") (pintype "passive"))
    )
    (net (code "65") (name "Net-(X1A-27)") (class "Default")
      (node (ref "R34") (pin "2") (pinfunction "2_2") (pintype "passive"))
      (node (ref "X1") (pin "A27") (pinfunction "27_A27") (pintype "passive"))
    )
    (net (code "66") (name "Net-(X1A-28)") (class "Default")
      (node (ref "R33") (pin "2") (pinfunction "2_2") (pintype "passive"))
      (node (ref "X1") (pin "A28") (pinfunction "28_A28") (pintype "passive"))
    )
    (net (code "67") (name "Net-(X1B-17)") (class "Default")
      (node (ref "R24") (pin "2") (pinfunction "2_2") (pintype "passive"))
      (node (ref "X1") (pin "B17") (pinfunction "17_B17") (pintype "passive"))
    )
    (net (code "68") (name "Net-(X1B-18)") (class "Default")
      (node (ref "R23") (pin "2") (pinfunction "2_2") (pintype "passive"))
      (node (ref "X1") (pin "B18") (pinfunction "18_B18") (pintype "passive"))
    )
    (net (code "69") (name "Net-(X1B-19)") (class "Default")
      (node (ref "R22") (pin "2") (pinfunction "2_2") (pintype "passive"))
      (node (ref "X1") (pin "B19") (pinfunction "19_B19") (pintype "passive"))
    )
    (net (code "70") (name "Net-(X1B-20)") (class "Default")
      (node (ref "R21") (pin "2") (pinfunction "2_2") (pintype "passive"))
      (node (ref "X1") (pin "B20") (pinfunction "20_B20") (pintype "passive"))
    )
    (net (code "71") (name "Net-(X1B-21)") (class "Default")
      (node (ref "R20") (pin "2") (pinfunction "2_2") (pintype "passive"))
      (node (ref "X1") (pin "B21") (pinfunction "21_B21") (pintype "passive"))
    )
    (net (code "72") (name "Net-(X1B-22)") (class "Default")
      (node (ref "R19") (pin "2") (pinfunction "2_2") (pintype "passive"))
      (node (ref "X1") (pin "B22") (pinfunction "22_B22") (pintype "passive"))
    )
    (net (code "73") (name "Net-(X1B-23)") (class "Default")
      (node (ref "R18") (pin "2") (pinfunction "2_2") (pintype "passive"))
      (node (ref "X1") (pin "B23") (pinfunction "23_B23") (pintype "passive"))
    )
    (net (code "74") (name "Net-(X1B-24)") (class "Default")
      (node (ref "R17") (pin "2") (pinfunction "2_2") (pintype "passive"))
      (node (ref "X1") (pin "B24") (pinfunction "24_B24") (pintype "passive"))
    )
    (net (code "75") (name "SCK{slash}H_SYNC") (class "Default")
      (node (ref "J1") (pin "14") (pinfunction "P$1_14") (pintype "bidirectional"))
      (node (ref "X1") (pin "B28") (pinfunction "28_B28") (pintype "passive"))
    )
    (net (code "76") (name "SLOT_SPI_CLK") (class "Default")
      (node (ref "X1") (pin "B1") (pinfunction "1_B1") (pintype "passive"))
    )
    (net (code "77") (name "SLOT_SPI_MISO") (class "Default")
      (node (ref "X1") (pin "B3") (pinfunction "3_B3") (pintype "passive"))
    )
    (net (code "78") (name "SLOT_SPI_MOSI") (class "Default")
      (node (ref "X1") (pin "B2") (pinfunction "2_B2") (pintype "passive"))
    )
    (net (code "79") (name "VCC_DAC") (class "Default")
      (node (ref "C21") (pin "2") (pinfunction "2_2") (pintype "passive"))
      (node (ref "C5") (pin "2") (pinfunction "2_2") (pintype "passive"))
      (node (ref "C6") (pin "2") (pinfunction "2_2") (pintype "passive"))
      (node (ref "C7") (pin "2") (pinfunction "2_2") (pintype "passive"))
      (node (ref "C8") (pin "2") (pinfunction "2_2") (pintype "passive"))
      (node (ref "IC3") (pin "P$14") (pinfunction "AVDD_P$14") (pintype "power_in"))
      (node (ref "IC3") (pin "P$8") (pinfunction "HPVDD_P$8") (pintype "power_in"))
      (node (ref "L6") (pin "2") (pinfunction "2_2") (pintype "passive"))
    )
    (net (code "80") (name "unconnected-(IC3-LOUT-PadP$12)") (class "Default")
      (node (ref "IC3") (pin "P$12") (pinfunction "LOUT_P$12") (pintype "output"))
    )
    (net (code "81") (name "unconnected-(IC3-ROUT-PadP$13)") (class "Default")
      (node (ref "IC3") (pin "P$13") (pinfunction "ROUT_P$13") (pintype "output"))
    )
    (net (code "82") (name "unconnected-(IC3-XTI{slash}MCLK-PadP$25)") (class "Default")
      (node (ref "IC3") (pin "P$25") (pinfunction "XTI/MCLK_P$25") (pintype "input"))
    )
    (net (code "83") (name "unconnected-(J1C-P$1-Pad11)") (class "Default")
      (node (ref "J1") (pin "11") (pinfunction "P$1_11") (pintype "bidirectional"))
    )
    (net (code "84") (name "unconnected-(J1D-P$1-Pad12)") (class "Default")
      (node (ref "J1") (pin "12") (pinfunction "P$1_12") (pintype "bidirectional"))
    )
    (net (code "85") (name "unconnected-(J1G-P$1-Pad15)") (class "Default")
      (node (ref "J1") (pin "15") (pinfunction "P$1_15") (pintype "bidirectional"))
    )
    (net (code "86") (name "unconnected-(J1J-P$1-Pad4)") (class "Default")
      (node (ref "J1") (pin "4") (pinfunction "P$1_4") (pintype "bidirectional"))
    )
    (net (code "87") (name "unconnected-(J1O-P$1-Pad9)") (class "Default")
      (node (ref "J1") (pin "9") (pinfunction "P$1_9") (pintype "bidirectional"))
    )
    (net (code "88") (name "unconnected-(X1A-11-PadA11)") (class "Default")
      (node (ref "X1") (pin "A11") (pinfunction "11_A11") (pintype "passive"))
    )
    (net (code "89") (name "unconnected-(X1A-12-PadA12)") (class "Default")
      (node (ref "X1") (pin "A12") (pinfunction "12_A12") (pintype "passive"))
    )
    (net (code "90") (name "unconnected-(X1A-13-PadA13)") (class "Default")
      (node (ref "X1") (pin "A13") (pinfunction "13_A13") (pintype "passive"))
    )
    (net (code "91") (name "unconnected-(X1A-14-PadA14)") (class "Default")
      (node (ref "X1") (pin "A14") (pinfunction "14_A14") (pintype "passive"))
    )
    (net (code "92") (name "unconnected-(X1A-15-PadA15)") (class "Default")
      (node (ref "X1") (pin "A15") (pinfunction "15_A15") (pintype "passive"))
    )
    (net (code "93") (name "unconnected-(X1A-16-PadA16)") (class "Default")
      (node (ref "X1") (pin "A16") (pinfunction "16_A16") (pintype "passive"))
    )
    (net (code "94") (name "unconnected-(X1B-8-PadB8)") (class "Default")
      (node (ref "X1") (pin "B8") (pinfunction "8_B8") (pintype "passive"))
    )
    (net (code "95") (name "unconnected-(X1B-9-PadB9)") (class "Default")
      (node (ref "X1") (pin "B9") (pinfunction "9_B9") (pintype "passive"))
    )
    (net (code "96") (name "unconnected-(X1B-10-PadB10)") (class "Default")
      (node (ref "X1") (pin "B10") (pinfunction "10_B10") (pintype "passive"))
    )
    (net (code "97") (name "unconnected-(X1B-11-PadB11)") (class "Default")
      (node (ref "X1") (pin "B11") (pinfunction "11_B11") (pintype "passive"))
    )
    (net (code "98") (name "unconnected-(X1B-12-PadB12)") (class "Default")
      (node (ref "X1") (pin "B12") (pinfunction "12_B12") (pintype "passive"))
    )
    (net (code "99") (name "unconnected-(X1B-13-PadB13)") (class "Default")
      (node (ref "X1") (pin "B13") (pinfunction "13_B13") (pintype "passive"))
    )
    (net (code "100") (name "unconnected-(X1B-14-PadB14)") (class "Default")
      (node (ref "X1") (pin "B14") (pinfunction "14_B14") (pintype "passive"))
    )
    (net (code "101") (name "unconnected-(X1B-15-PadB15)") (class "Default")
      (node (ref "X1") (pin "B15") (pinfunction "15_B15") (pintype "passive"))
    )
    (net (code "102") (name "unconnected-(X1B-16-PadB16)") (class "Default")
      (node (ref "X1") (pin "B16") (pinfunction "16_B16") (pintype "passive"))
    )
  )
)
